# PCB_ALIM_diodes_adapt_es_version_8.net
KiCad netlist of a schematic drawn in EAGLE
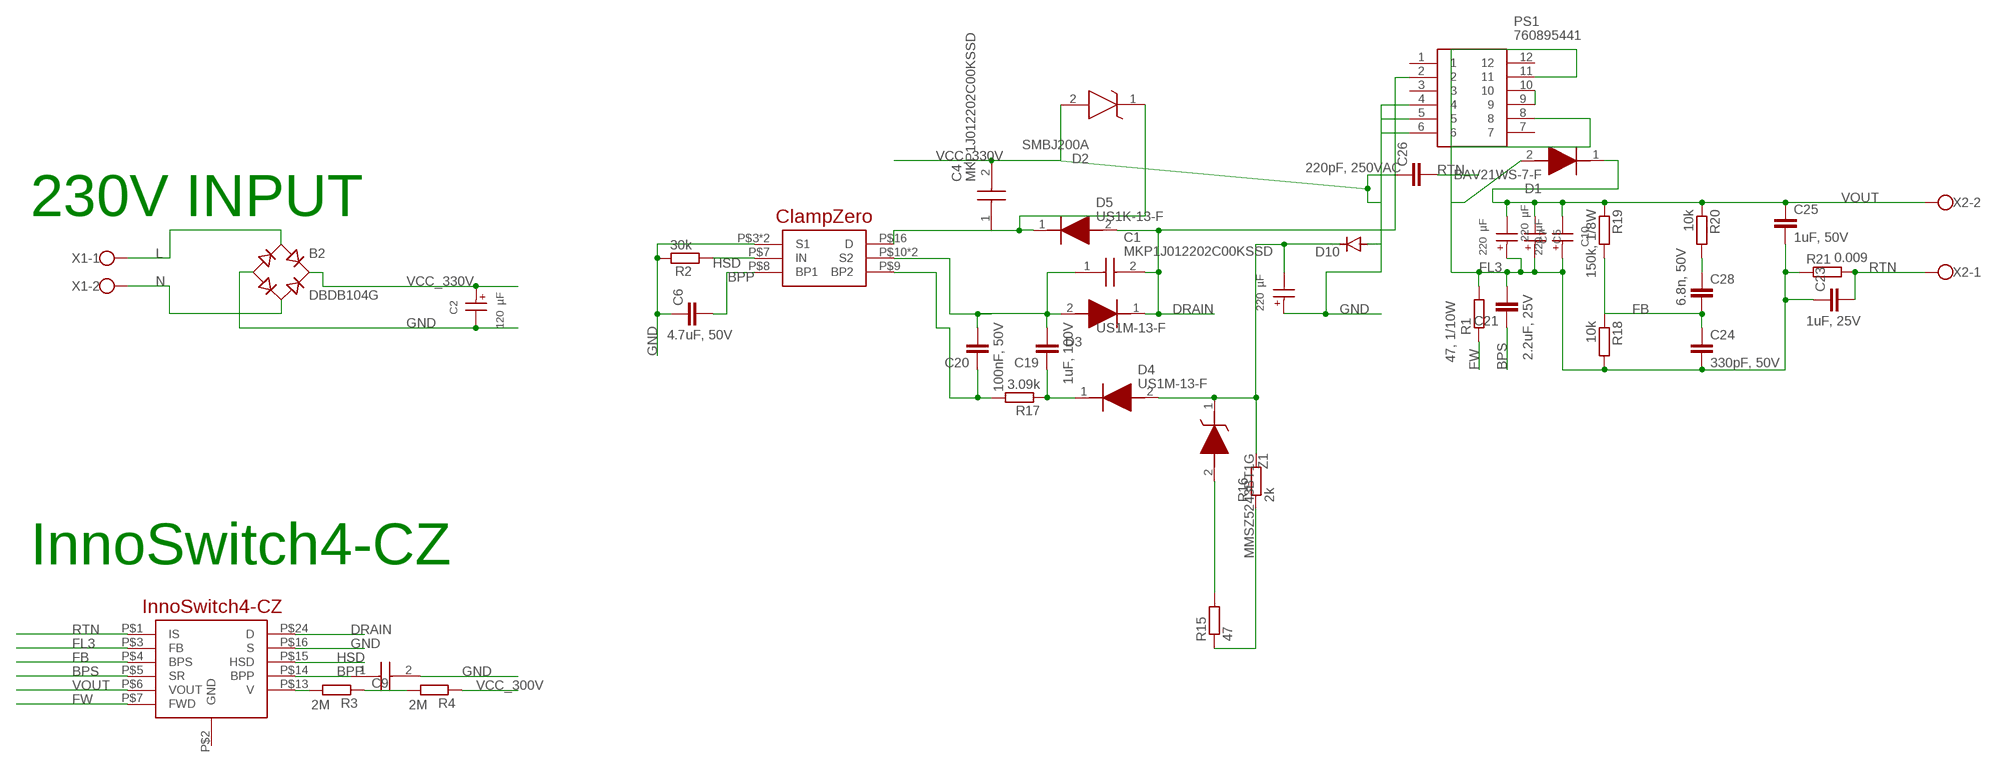
[diagram p0: schematic, sheet 1]

(export (version "E")
  (design (tool "Eeschema 10.0.6"))
  (components
    (comp (ref "B2")
      (value "DBDB104G")
      (footprint "eagle-import:DB")
      (libsource (lib "eagle-import") (part "DB?GDB104"))
    )
    (comp (ref "C1")
      (value "MKP1J012202C00KSSD")
      (footprint "eagle-import:MKP1J012202C00KSSD")
      (fields (field (name "MOUSER_PART_NUMBER") "505-M102200/630/10"))
      (libsource (lib "eagle-import") (part "MKP1J012202C00KSSD"))
    )
    (comp (ref "C2")
      (value "120 µF")
      (footprint "eagle-import:WCAP-ATG8_18X41X7.5(DXL)")
      (libsource (lib "eagle-import") (part "WCAP-ATG8_18X41_860011381013"))
    )
    (comp (ref "C4")
      (value "MKP1J012202C00KSSD")
      (footprint "eagle-import:MKP1J012202C00KSSD")
      (fields (field (name "MOUSER_PART_NUMBER") "505-M102200/630/10"))
      (libsource (lib "eagle-import") (part "MKP1J012202C00KSSD"))
    )
    (comp (ref "C5")
      (value "220 µF")
      (footprint "eagle-import:WCAP-ASLI_10X10.5(DXL)")
      (libsource (lib "eagle-import") (part "WCAP-ASLI_10X10.5_865080657018"))
    )
    (comp (ref "C6")
      (value "4.7uF, 50V")
      (footprint "eagle-import:C0603")
      (libsource (lib "eagle-import") (part "C-EUC0603"))
    )
    (comp (ref "C7")
      (value "220 µF")
      (footprint "eagle-import:WCAP-ASLI_10X10.5(DXL)")
      (libsource (lib "eagle-import") (part "WCAP-ASLI_10X10.5_865080657018"))
    )
    (comp (ref "C8")
      (value "220 µF")
      (footprint "eagle-import:WCAP-ASLI_10X10.5(DXL)")
      (libsource (lib "eagle-import") (part "WCAP-ASLI_10X10.5_865080657018"))
    )
    (comp (ref "C9")
      (value "MKP1J012202C00KSSD")
      (footprint "eagle-import:MKP1J012202C00KSSD")
      (fields (field (name "MOUSER_PART_NUMBER") "505-M102200/630/10"))
      (libsource (lib "eagle-import") (part "MKP1J012202C00KSSD"))
    )
    (comp (ref "C10")
      (value "220 µF")
      (footprint "eagle-import:WCAP-ASLI_10X10.5(DXL)")
      (libsource (lib "eagle-import") (part "WCAP-ASLI_10X10.5_865080657018"))
    )
    (comp (ref "C19")
      (value "1uF, 100V")
      (footprint "eagle-import:C0603")
      (libsource (lib "eagle-import") (part "C-EUC0603"))
    )
    (comp (ref "C20")
      (value "100nF, 50V")
      (footprint "eagle-import:C0603")
      (libsource (lib "eagle-import") (part "C-EUC0603"))
    )
    (comp (ref "C21")
      (value "2.2uF, 25V")
      (footprint "eagle-import:C0603")
      (libsource (lib "eagle-import") (part "C-EUC0603"))
    )
    (comp (ref "C23")
      (value "1uF, 25V")
      (footprint "eagle-import:C0603")
      (libsource (lib "eagle-import") (part "C-EUC0603"))
    )
    (comp (ref "C24")
      (value "330pF, 50V")
      (footprint "eagle-import:C0603")
      (libsource (lib "eagle-import") (part "C-EUC0603"))
    )
    (comp (ref "C25")
      (value "1uF, 50V")
      (footprint "eagle-import:C0603")
      (libsource (lib "eagle-import") (part "C-EUC0603"))
    )
    (comp (ref "C26")
      (value "220pF, 250VAC")
      (footprint "eagle-import:C0603")
      (libsource (lib "eagle-import") (part "C-EUC0603"))
    )
    (comp (ref "C28")
      (value "6.8n, 50V")
      (footprint "eagle-import:C0603")
      (libsource (lib "eagle-import") (part "C-EUC0603"))
    )
    (comp (ref "D1")
      (value "BAV21WS-7-F")
      (footprint "eagle-import:SOD2513X120N")
      (fields (field (name "MOUSER_PART_NUMBER") "621-BAV21WS-F"))
      (libsource (lib "eagle-import") (part "BAV21WS-7-F"))
    )
    (comp (ref "D2")
      (value "SMBJ200A")
      (footprint "eagle-import:DIOM5436X261N")
      (fields (field (name "MOUSER_PART_NUMBER") "576-SMBJ200A"))
      (libsource (lib "eagle-import") (part "SMBJ200A"))
    )
    (comp (ref "D3")
      (value "US1M-13-F")
      (footprint "eagle-import:SODFL5226X240N")
      (fields (field (name "MOUSER_PART_NUMBER") "621-US1M-F"))
      (libsource (lib "eagle-import") (part "US1M-13-F"))
    )
    (comp (ref "D4")
      (value "US1M-13-F")
      (footprint "eagle-import:SODFL5226X240N")
      (fields (field (name "MOUSER_PART_NUMBER") "621-US1M-F"))
      (libsource (lib "eagle-import") (part "US1M-13-F"))
    )
    (comp (ref "D5")
      (value "US1K-13-F")
      (footprint "eagle-import:DIOM5226X240N")
      (fields (field (name "MOUSER_PART_NUMBER") "621-US1K-F"))
      (libsource (lib "eagle-import") (part "US1K-13-F"))
    )
    (comp (ref "D10")
      (value "1N4933")
      (footprint "eagle-import:DO41-10")
      (libsource (lib "eagle-import") (part "1N4933"))
    )
    (comp (ref "PS1")
      (value "760895441")
      (footprint "eagle-import:DIPS2800W80P550L3600H2600Q12N")
      (fields (field (name "MOUSER_PART_NUMBER") "710-760895441"))
      (libsource (lib "eagle-import") (part "760895441"))
    )
    (comp (ref "R1")
      (value "47, 1/10W")
      (footprint "eagle-import:R0603")
      (libsource (lib "eagle-import") (part "R-EU_R0603"))
    )
    (comp (ref "R2")
      (value "30k")
      (footprint "eagle-import:R0603")
      (libsource (lib "eagle-import") (part "R-EU_R0603"))
    )
    (comp (ref "R3")
      (value "2M")
      (footprint "eagle-import:R0603")
      (libsource (lib "eagle-import") (part "R-EU_R0603"))
    )
    (comp (ref "R4")
      (value "2M")
      (footprint "eagle-import:R0603")
      (libsource (lib "eagle-import") (part "R-EU_R0603"))
    )
    (comp (ref "R15")
      (value "47")
      (footprint "eagle-import:R0603")
      (libsource (lib "eagle-import") (part "R-EU_R0603"))
    )
    (comp (ref "R16")
      (value "2k")
      (footprint "eagle-import:R0603")
      (libsource (lib "eagle-import") (part "R-EU_R0603"))
    )
    (comp (ref "R17")
      (value "3.09k")
      (footprint "eagle-import:R0603")
      (libsource (lib "eagle-import") (part "R-EU_R0603"))
    )
    (comp (ref "R18")
      (value "10k")
      (footprint "eagle-import:R0603")
      (libsource (lib "eagle-import") (part "R-EU_R0603"))
    )
    (comp (ref "R19")
      (value "150k, 1/8W")
      (footprint "eagle-import:R0603")
      (libsource (lib "eagle-import") (part "R-EU_R0603"))
    )
    (comp (ref "R20")
      (value "10k")
      (footprint "eagle-import:R0603")
      (libsource (lib "eagle-import") (part "R-EU_R0603"))
    )
    (comp (ref "R21")
      (value "0.009")
      (footprint "eagle-import:R0603")
      (libsource (lib "eagle-import") (part "R-EU_R0603"))
    )
    (comp (ref "U$3")
      (value "CLAMPZERO")
      (footprint "eagle-import:MINSOP-16A")
      (libsource (lib "eagle-import") (part "CLAMPZERO"))
    )
    (comp (ref "U$4")
      (value "INNOSWITCH4-CZ")
      (footprint "eagle-import:INSOP-24D")
      (libsource (lib "eagle-import") (part "INNOSWITCH4-CZ"))
    )
    (comp (ref "X1")
      (value "W237-102")
      (footprint "eagle-import:W237-102")
      (fields (field (name "MPN") "237-102"))
      (libsource (lib "eagle-import") (part "W237-102"))
    )
    (comp (ref "X2")
      (value "W237-102")
      (footprint "eagle-import:W237-102")
      (fields (field (name "MPN") "237-102"))
      (libsource (lib "eagle-import") (part "W237-102"))
    )
    (comp (ref "Z1")
      (value "MMSZ5243BT1G")
      (footprint "eagle-import:SOD3716X135N")
      (fields (field (name "MOUSER_PART_NUMBER") "863-MMSZ5243BT1G"))
      (libsource (lib "eagle-import") (part "MMSZ5243BT1G"))
    )
  )
  (nets
    (net (code "1") (name "BPP") (class "Default")
      (node (ref "C6") (pin "2") (pinfunction "2_2") (pintype "passive"))
      (node (ref "C9") (pin "1") (pinfunction "1_1") (pintype "bidirectional"))
      (node (ref "U$3") (pin "P$8") (pinfunction "BP1_P$8") (pintype "bidirectional"))
      (node (ref "U$4") (pin "P$14") (pinfunction "BPP_P$14") (pintype "bidirectional"))
    )
    (net (code "2") (name "BPS") (class "Default")
      (node (ref "C21") (pin "1") (pinfunction "1_1") (pintype "passive"))
      (node (ref "U$4") (pin "P$5") (pinfunction "SR_P$5") (pintype "bidirectional"))
    )
    (net (code "3") (name "DRAIN") (class "Default")
      (node (ref "C1") (pin "2") (pinfunction "2_2") (pintype "bidirectional"))
      (node (ref "D3") (pin "1") (pinfunction "K_1") (pintype "bidirectional"))
      (node (ref "D5") (pin "2") (pinfunction "A_2") (pintype "bidirectional"))
      (node (ref "PS1") (pin "2") (pinfunction "2_2") (pintype "bidirectional"))
      (node (ref "U$4") (pin "P$24") (pinfunction "D_P$24") (pintype "bidirectional"))
    )
    (net (code "4") (name "FB") (class "Default")
      (node (ref "C24") (pin "1") (pinfunction "1_1") (pintype "passive"))
      (node (ref "C28") (pin "2") (pinfunction "2_2") (pintype "passive"))
      (node (ref "R18") (pin "1") (pinfunction "1_1") (pintype "passive"))
      (node (ref "R19") (pin "2") (pinfunction "2_2") (pintype "passive"))
      (node (ref "U$4") (pin "P$4") (pinfunction "BPS_P$4") (pintype "bidirectional"))
    )
    (net (code "5") (name "FL3") (class "Default")
      (node (ref "C10") (pin "1") (pinfunction "+_1") (pintype "passive"))
      (node (ref "C21") (pin "2") (pinfunction "2_2") (pintype "passive"))
      (node (ref "C23") (pin "1") (pinfunction "1_1") (pintype "passive"))
      (node (ref "C24") (pin "2") (pinfunction "2_2") (pintype "passive"))
      (node (ref "C25") (pin "2") (pinfunction "2_2") (pintype "passive"))
      (node (ref "C5") (pin "1") (pinfunction "+_1") (pintype "passive"))
      (node (ref "C7") (pin "1") (pinfunction "+_1") (pintype "passive"))
      (node (ref "PS1") (pin "11") (pinfunction "11_11") (pintype "bidirectional"))
      (node (ref "R1") (pin "2") (pinfunction "2_2") (pintype "passive"))
      (node (ref "R18") (pin "2") (pinfunction "2_2") (pintype "passive"))
      (node (ref "R21") (pin "1") (pinfunction "1_1") (pintype "passive"))
      (node (ref "U$4") (pin "P$3") (pinfunction "FB_P$3") (pintype "bidirectional"))
    )
    (net (code "6") (name "FW") (class "Default")
      (node (ref "R1") (pin "1") (pinfunction "1_1") (pintype "passive"))
      (node (ref "U$4") (pin "P$7") (pinfunction "FWD_P$7") (pintype "bidirectional"))
    )
    (net (code "7") (name "GND") (class "Default")
      (node (ref "B2") (pin "-") (pinfunction "-_-") (pintype "passive"))
      (node (ref "C2") (pin "2") (pinfunction "-_2") (pintype "passive"))
      (node (ref "C6") (pin "1") (pinfunction "1_1") (pintype "passive"))
      (node (ref "C8") (pin "1") (pinfunction "+_1") (pintype "passive"))
      (node (ref "C9") (pin "2") (pinfunction "2_2") (pintype "bidirectional"))
      (node (ref "PS1") (pin "6") (pinfunction "6_6") (pintype "bidirectional"))
      (node (ref "R2") (pin "2") (pinfunction "2_2") (pintype "passive"))
      (node (ref "U$3") (pin "P$3") (pinfunction "S1_P$3") (pintype "bidirectional"))
      (node (ref "U$3") (pin "P$6") (pinfunction "S1_P$6") (pintype "bidirectional"))
      (node (ref "U$4") (pin "P$16") (pinfunction "S_P$16") (pintype "bidirectional"))
    )
    (net (code "8") (name "HSD") (class "Default")
      (node (ref "R2") (pin "1") (pinfunction "1_1") (pintype "passive"))
      (node (ref "U$3") (pin "P$7") (pinfunction "IN_P$7") (pintype "bidirectional"))
      (node (ref "U$4") (pin "P$15") (pinfunction "HSD_P$15") (pintype "bidirectional"))
    )
    (net (code "9") (name "L") (class "Default")
      (node (ref "B2") (pin "AC1") (pinfunction "AC1_AC1") (pintype "passive"))
      (node (ref "X1") (pin "1") (pinfunction "KL_1") (pintype "passive"))
    )
    (net (code "10") (name "N") (class "Default")
      (node (ref "B2") (pin "AC2") (pinfunction "AC2_AC2") (pintype "passive"))
      (node (ref "X1") (pin "2") (pinfunction "KL_2") (pintype "passive"))
    )
    (net (code "11") (name "Net-(C8--)") (class "Default")
      (node (ref "C8") (pin "2") (pinfunction "-_2") (pintype "passive"))
      (node (ref "D10") (pin "C") (pinfunction "C_C") (pintype "passive"))
      (node (ref "D4") (pin "2") (pinfunction "A_2") (pintype "bidirectional"))
      (node (ref "R16") (pin "2") (pinfunction "2_2") (pintype "passive"))
      (node (ref "Z1") (pin "1") (pinfunction "K_1") (pintype "bidirectional"))
    )
    (net (code "12") (name "Net-(C28-Pad1)") (class "Default")
      (node (ref "C28") (pin "1") (pinfunction "1_1") (pintype "passive"))
      (node (ref "R20") (pin "2") (pinfunction "2_2") (pintype "passive"))
    )
    (net (code "13") (name "Net-(D1-A)") (class "Default")
      (node (ref "D1") (pin "2") (pinfunction "A_2") (pintype "bidirectional"))
      (node (ref "PS1") (pin "8") (pinfunction "8_8") (pintype "bidirectional"))
    )
    (net (code "14") (name "Net-(D2-K)") (class "Default")
      (node (ref "C4") (pin "1") (pinfunction "1_1") (pintype "bidirectional"))
      (node (ref "D2") (pin "1") (pinfunction "K_1") (pintype "bidirectional"))
      (node (ref "D5") (pin "1") (pinfunction "K_1") (pintype "bidirectional"))
      (node (ref "U$3") (pin "P$16") (pinfunction "D_P$16") (pintype "bidirectional"))
    )
    (net (code "15") (name "Net-(D3-A)") (class "Default")
      (node (ref "C1") (pin "1") (pinfunction "1_1") (pintype "bidirectional"))
      (node (ref "C19") (pin "2") (pinfunction "2_2") (pintype "passive"))
      (node (ref "C20") (pin "2") (pinfunction "2_2") (pintype "passive"))
      (node (ref "D3") (pin "2") (pinfunction "A_2") (pintype "bidirectional"))
      (node (ref "U$3") (pin "P$10") (pinfunction "S2_P$10") (pintype "bidirectional"))
      (node (ref "U$3") (pin "P$11") (pinfunction "S2_P$11") (pintype "bidirectional"))
    )
    (net (code "16") (name "Net-(D4-K)") (class "Default")
      (node (ref "C19") (pin "1") (pinfunction "1_1") (pintype "passive"))
      (node (ref "D4") (pin "1") (pinfunction "K_1") (pintype "bidirectional"))
      (node (ref "R17") (pin "1") (pinfunction "1_1") (pintype "passive"))
    )
    (net (code "17") (name "Net-(D10-PadA)") (class "Default")
      (node (ref "D10") (pin "A") (pinfunction "A_A") (pintype "passive"))
      (node (ref "PS1") (pin "5") (pinfunction "5_5") (pintype "bidirectional"))
    )
    (net (code "18") (name "Net-(PS1-Pad10)") (class "Default")
      (node (ref "PS1") (pin "10") (pinfunction "10_10") (pintype "bidirectional"))
      (node (ref "PS1") (pin "9") (pinfunction "9_9") (pintype "bidirectional"))
    )
    (net (code "19") (name "Net-(R3-Pad1)") (class "Default")
      (node (ref "R3") (pin "1") (pinfunction "1_1") (pintype "passive"))
      (node (ref "R4") (pin "2") (pinfunction "2_2") (pintype "passive"))
    )
    (net (code "20") (name "Net-(R15-Pad1)") (class "Default")
      (node (ref "R15") (pin "1") (pinfunction "1_1") (pintype "passive"))
      (node (ref "R16") (pin "1") (pinfunction "1_1") (pintype "passive"))
    )
    (net (code "21") (name "Net-(U$3-BP2)") (class "Default")
      (node (ref "C20") (pin "1") (pinfunction "1_1") (pintype "passive"))
      (node (ref "R17") (pin "2") (pinfunction "2_2") (pintype "passive"))
      (node (ref "U$3") (pin "P$9") (pinfunction "BP2_P$9") (pintype "bidirectional"))
    )
    (net (code "22") (name "Net-(U$4-V)") (class "Default")
      (node (ref "R3") (pin "2") (pinfunction "2_2") (pintype "passive"))
      (node (ref "U$4") (pin "P$13") (pinfunction "V_P$13") (pintype "bidirectional"))
    )
    (net (code "23") (name "Net-(Z1-A)") (class "Default")
      (node (ref "R15") (pin "2") (pinfunction "2_2") (pintype "passive"))
      (node (ref "Z1") (pin "2") (pinfunction "A_2") (pintype "bidirectional"))
    )
    (net (code "24") (name "RTN") (class "Default")
      (node (ref "C23") (pin "2") (pinfunction "2_2") (pintype "passive"))
      (node (ref "C26") (pin "2") (pinfunction "2_2") (pintype "passive"))
      (node (ref "R21") (pin "2") (pinfunction "2_2") (pintype "passive"))
      (node (ref "U$4") (pin "P$1") (pinfunction "IS_P$1") (pintype "bidirectional"))
      (node (ref "X2") (pin "1") (pinfunction "KL_1") (pintype "passive"))
    )
    (net (code "25") (name "VCC_300V") (class "Default")
      (node (ref "R4") (pin "1") (pinfunction "1_1") (pintype "passive"))
    )
    (net (code "26") (name "VCC_330V") (class "Default")
      (node (ref "B2") (pin "+") (pinfunction "+_+") (pintype "passive"))
      (node (ref "C2") (pin "1") (pinfunction "+_1") (pintype "passive"))
      (node (ref "C26") (pin "1") (pinfunction "1_1") (pintype "passive"))
      (node (ref "C4") (pin "2") (pinfunction "2_2") (pintype "bidirectional"))
      (node (ref "D2") (pin "2") (pinfunction "A_2") (pintype "bidirectional"))
      (node (ref "PS1") (pin "4") (pinfunction "4_4") (pintype "bidirectional"))
    )
    (net (code "27") (name "VOUT") (class "Default")
      (node (ref "C10") (pin "2") (pinfunction "-_2") (pintype "passive"))
      (node (ref "C25") (pin "1") (pinfunction "1_1") (pintype "passive"))
      (node (ref "C5") (pin "2") (pinfunction "-_2") (pintype "passive"))
      (node (ref "C7") (pin "2") (pinfunction "-_2") (pintype "passive"))
      (node (ref "D1") (pin "1") (pinfunction "K_1") (pintype "bidirectional"))
      (node (ref "R19") (pin "1") (pinfunction "1_1") (pintype "passive"))
      (node (ref "R20") (pin "1") (pinfunction "1_1") (pintype "passive"))
      (node (ref "U$4") (pin "P$6") (pinfunction "VOUT_P$6") (pintype "bidirectional"))
      (node (ref "X2") (pin "2") (pinfunction "KL_2") (pintype "passive"))
    )
    (net (code "28") (name "unconnected-(PS1-Pad1)") (class "Default")
      (node (ref "PS1") (pin "1") (pinfunction "1_1") (pintype "bidirectional"))
    )
    (net (code "29") (name "unconnected-(PS1-Pad3)") (class "Default")
      (node (ref "PS1") (pin "3") (pinfunction "3_3") (pintype "bidirectional"))
    )
    (net (code "30") (name "unconnected-(PS1-Pad7)") (class "Default")
      (node (ref "PS1") (pin "7") (pinfunction "7_7") (pintype "bidirectional"))
    )
    (net (code "31") (name "unconnected-(PS1-Pad12)") (class "Default")
      (node (ref "PS1") (pin "12") (pinfunction "12_12") (pintype "bidirectional"))
    )
    (net (code "32") (name "unconnected-(U$4-GND-PadP$2)") (class "Default")
      (node (ref "U$4") (pin "P$2") (pinfunction "GND_P$2") (pintype "bidirectional"))
    )
  )
)
